# Toggle_Switch.net
KiCad netlist of a schematic drawn in EAGLE
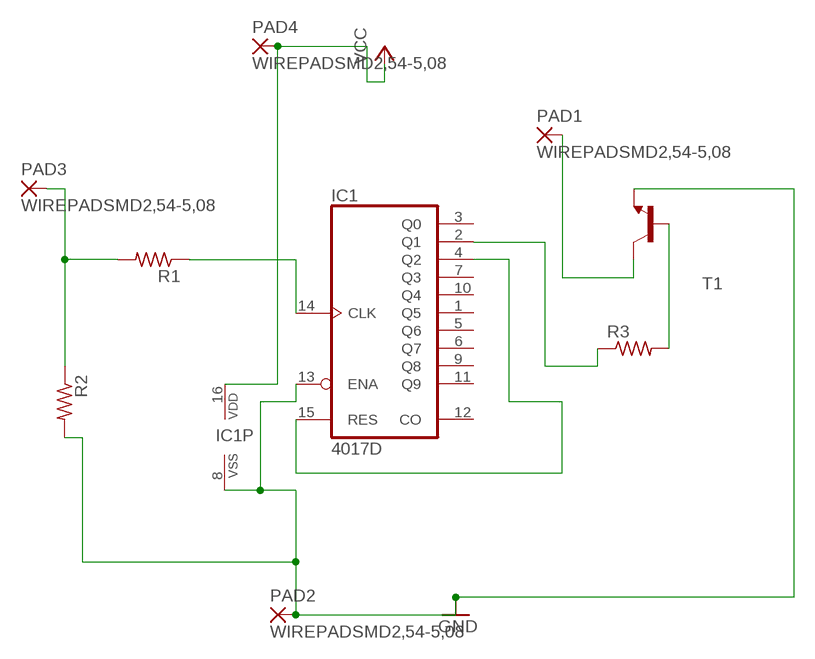
[diagram p0: schematic, sheet 1]

(export (version "E")
  (design (tool "Eeschema 10.0.6"))
  (components
    (comp (ref "IC1")
      (value "4017D")
      (footprint "eagle-import:SO16")
      (libsource (lib "eagle-import") (part "4017D"))
    )
    (comp (ref "PAD1")
      (value "WIREPADSMD2,54-5,08")
      (footprint "eagle-import:SMD2,54-5,08")
      (libsource (lib "eagle-import") (part "WIREPADSMD2,54-5,08"))
    )
    (comp (ref "PAD2")
      (value "WIREPADSMD2,54-5,08")
      (footprint "eagle-import:SMD2,54-5,08")
      (libsource (lib "eagle-import") (part "WIREPADSMD2,54-5,08"))
    )
    (comp (ref "PAD3")
      (value "WIREPADSMD2,54-5,08")
      (footprint "eagle-import:SMD2,54-5,08")
      (libsource (lib "eagle-import") (part "WIREPADSMD2,54-5,08"))
    )
    (comp (ref "PAD4")
      (value "WIREPADSMD2,54-5,08")
      (footprint "eagle-import:SMD2,54-5,08")
      (libsource (lib "eagle-import") (part "WIREPADSMD2,54-5,08"))
    )
    (comp (ref "R1")
      (value "R-US_0207/7")
      (footprint "eagle-import:0207_7")
      (libsource (lib "eagle-import") (part "R-US_0207/7"))
    )
    (comp (ref "R2")
      (value "R-US_0207/7")
      (footprint "eagle-import:0207_7")
      (libsource (lib "eagle-import") (part "R-US_0207/7"))
    )
    (comp (ref "R3")
      (value "R-US_0207/7")
      (footprint "eagle-import:0207_7")
      (libsource (lib "eagle-import") (part "R-US_0207/7"))
    )
    (comp (ref "T1")
      (value "BC639-NPN-TO92-ECB")
      (footprint "eagle-import:TO92-ECB")
      (libsource (lib "eagle-import") (part "-NPN-TO92-ECBBC639"))
    )
  )
  (nets
    (net (code "1") (name "GND") (class "Default")
      (node (ref "IC1") (pin "13") (pinfunction "ENA_13") (pintype "input"))
      (node (ref "IC1") (pin "8") (pinfunction "VSS_8") (pintype "power_in"))
      (node (ref "PAD2") (pin "1") (pinfunction "P_1") (pintype "passive"))
      (node (ref "R2") (pin "2") (pinfunction "2_2") (pintype "passive"))
      (node (ref "T1") (pin "E") (pinfunction "E_E") (pintype "passive"))
    )
    (net (code "2") (name "Net-(IC1A-CLK)") (class "Default")
      (node (ref "IC1") (pin "14") (pinfunction "CLK_14") (pintype "input"))
      (node (ref "R1") (pin "1") (pinfunction "1_1") (pintype "passive"))
    )
    (net (code "3") (name "Net-(IC1A-Q1)") (class "Default")
      (node (ref "IC1") (pin "2") (pinfunction "Q1_2") (pintype "output"))
      (node (ref "R3") (pin "1") (pinfunction "1_1") (pintype "passive"))
    )
    (net (code "4") (name "Net-(IC1A-Q2)") (class "Default")
      (node (ref "IC1") (pin "15") (pinfunction "RES_15") (pintype "input"))
      (node (ref "IC1") (pin "4") (pinfunction "Q2_4") (pintype "output"))
    )
    (net (code "5") (name "Net-(PAD1-P)") (class "Default")
      (node (ref "PAD1") (pin "1") (pinfunction "P_1") (pintype "passive"))
      (node (ref "T1") (pin "C") (pinfunction "C_C") (pintype "passive"))
    )
    (net (code "6") (name "Net-(PAD3-P)") (class "Default")
      (node (ref "PAD3") (pin "1") (pinfunction "P_1") (pintype "passive"))
      (node (ref "R1") (pin "2") (pinfunction "2_2") (pintype "passive"))
      (node (ref "R2") (pin "1") (pinfunction "1_1") (pintype "passive"))
    )
    (net (code "7") (name "Net-(R3-Pad2)") (class "Default")
      (node (ref "R3") (pin "2") (pinfunction "2_2") (pintype "passive"))
      (node (ref "T1") (pin "B") (pinfunction "B_B") (pintype "passive"))
    )
    (net (code "8") (name "VCC") (class "Default")
      (node (ref "IC1") (pin "16") (pinfunction "VDD_16") (pintype "power_in"))
      (node (ref "PAD4") (pin "1") (pinfunction "P_1") (pintype "passive"))
    )
    (net (code "9") (name "unconnected-(IC1A-CO-Pad12)") (class "Default")
      (node (ref "IC1") (pin "12") (pinfunction "CO_12") (pintype "output"))
    )
    (net (code "10") (name "unconnected-(IC1A-Q0-Pad3)") (class "Default")
      (node (ref "IC1") (pin "3") (pinfunction "Q0_3") (pintype "output"))
    )
    (net (code "11") (name "unconnected-(IC1A-Q3-Pad7)") (class "Default")
      (node (ref "IC1") (pin "7") (pinfunction "Q3_7") (pintype "output"))
    )
    (net (code "12") (name "unconnected-(IC1A-Q4-Pad10)") (class "Default")
      (node (ref "IC1") (pin "10") (pinfunction "Q4_10") (pintype "output"))
    )
    (net (code "13") (name "unconnected-(IC1A-Q5-Pad1)") (class "Default")
      (node (ref "IC1") (pin "1") (pinfunction "Q5_1") (pintype "output"))
    )
    (net (code "14") (name "unconnected-(IC1A-Q6-Pad5)") (class "Default")
      (node (ref "IC1") (pin "5") (pinfunction "Q6_5") (pintype "output"))
    )
    (net (code "15") (name "unconnected-(IC1A-Q7-Pad6)") (class "Default")
      (node (ref "IC1") (pin "6") (pinfunction "Q7_6") (pintype "output"))
    )
    (net (code "16") (name "unconnected-(IC1A-Q8-Pad9)") (class "Default")
      (node (ref "IC1") (pin "9") (pinfunction "Q8_9") (pintype "output"))
    )
    (net (code "17") (name "unconnected-(IC1A-Q9-Pad11)") (class "Default")
      (node (ref "IC1") (pin "11") (pinfunction "Q9_11") (pintype "output"))
    )
  )
)
